# ifusb_l.net
KiCad netlist of a schematic drawn in EAGLE
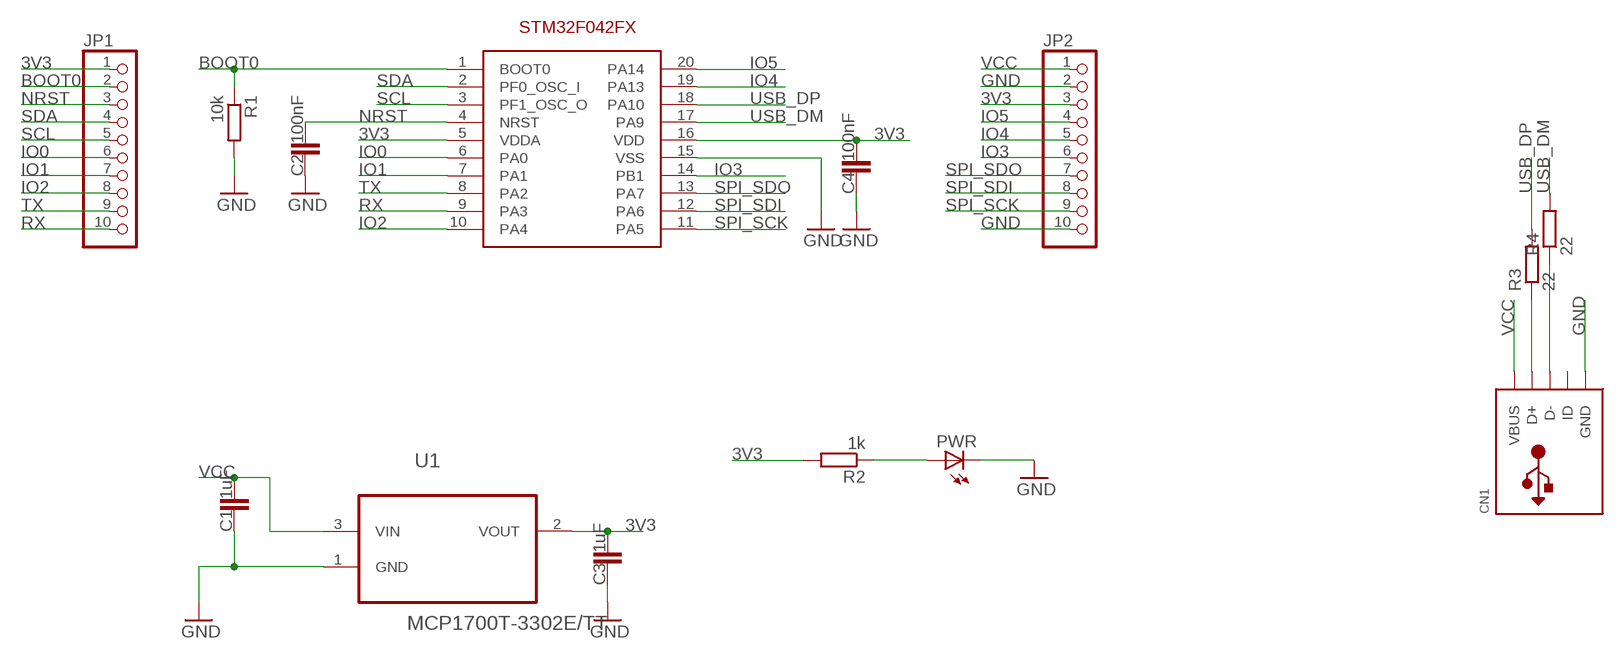
[diagram p0: schematic, sheet 1]

(export (version "E")
  (design (tool "Eeschema 10.0.6"))
  (components
    (comp (ref "C1")
      (value "1uF")
      (footprint "eagle-import:C0603K")
      (libsource (lib "eagle-import") (part "C-EUC0603K"))
    )
    (comp (ref "C2")
      (value "100nF")
      (footprint "eagle-import:C0603K")
      (libsource (lib "eagle-import") (part "C-EUC0603K"))
    )
    (comp (ref "C3")
      (value "1uF")
      (footprint "eagle-import:C0603K")
      (libsource (lib "eagle-import") (part "C-EUC0603K"))
    )
    (comp (ref "C4")
      (value "100nF")
      (footprint "eagle-import:C0603K")
      (libsource (lib "eagle-import") (part "C-EUC0603K"))
    )
    (comp (ref "CN1")
      (value "USBMOLEX")
      (footprint "eagle-import:USB-MINIB-THM-MOLEX")
      (libsource (lib "eagle-import") (part "USBMOLEX"))
    )
    (comp (ref "JP1")
      (value "HEADER-1X10ROUND")
      (footprint "eagle-import:1X10_ROUND")
      (libsource (lib "eagle-import") (part "HEADER-1X10ROUND"))
    )
    (comp (ref "JP2")
      (value "HEADER-1X10ROUND")
      (footprint "eagle-import:1X10_ROUND")
      (libsource (lib "eagle-import") (part "HEADER-1X10ROUND"))
    )
    (comp (ref "PWR")
      (value "LEDCHIP-LED0603")
      (footprint "eagle-import:CHIP-LED0603")
      (libsource (lib "eagle-import") (part "LEDCHIP-LED0603"))
    )
    (comp (ref "R1")
      (value "10k")
      (footprint "eagle-import:R0603")
      (libsource (lib "eagle-import") (part "R-EU_R0603"))
    )
    (comp (ref "R2")
      (value "1k")
      (footprint "eagle-import:R0603")
      (libsource (lib "eagle-import") (part "R-EU_R0603"))
    )
    (comp (ref "R3")
      (value "22")
      (footprint "eagle-import:R0603")
      (libsource (lib "eagle-import") (part "R-EU_R0603"))
    )
    (comp (ref "R4")
      (value "22")
      (footprint "eagle-import:R0603")
      (libsource (lib "eagle-import") (part "R-EU_R0603"))
    )
    (comp (ref "U1")
      (value "MCP1700T-3302E/TT")
      (footprint "eagle-import:SOT95P237X112-3N")
      (libsource (lib "eagle-import") (part "MCP1700T-3302E/TT"))
    )
    (comp (ref "U2")
      (value "STM32F042FX")
      (footprint "eagle-import:TSSOP20")
      (libsource (lib "eagle-import") (part "STM32F042FX"))
    )
  )
  (nets
    (net (code "1") (name "/3V3") (class "Default")
      (node (ref "C3") (pin "2") (pinfunction "2_2") (pintype "passive"))
      (node (ref "C4") (pin "2") (pinfunction "2_2") (pintype "passive"))
      (node (ref "JP1") (pin "1") (pinfunction "1_1") (pintype "passive"))
      (node (ref "JP2") (pin "3") (pinfunction "3_3") (pintype "passive"))
      (node (ref "R2") (pin "2") (pinfunction "2_2") (pintype "passive"))
      (node (ref "U1") (pin "2") (pinfunction "VOUT_2") (pintype "output"))
      (node (ref "U2") (pin "16") (pinfunction "VDD_16") (pintype "power_in"))
      (node (ref "U2") (pin "5") (pinfunction "VDDA_5") (pintype "power_in"))
    )
    (net (code "2") (name "/BOOT0") (class "Default")
      (node (ref "JP1") (pin "2") (pinfunction "2_2") (pintype "passive"))
      (node (ref "R1") (pin "1") (pinfunction "1_1") (pintype "passive"))
      (node (ref "U2") (pin "1") (pinfunction "BOOT0_1") (pintype "bidirectional"))
    )
    (net (code "3") (name "/IO0") (class "Default")
      (node (ref "JP1") (pin "6") (pinfunction "6_6") (pintype "passive"))
      (node (ref "U2") (pin "6") (pinfunction "PA0_6") (pintype "bidirectional"))
    )
    (net (code "4") (name "/IO1") (class "Default")
      (node (ref "JP1") (pin "7") (pinfunction "7_7") (pintype "passive"))
      (node (ref "U2") (pin "7") (pinfunction "PA1_7") (pintype "bidirectional"))
    )
    (net (code "5") (name "/IO2") (class "Default")
      (node (ref "JP1") (pin "8") (pinfunction "8_8") (pintype "passive"))
      (node (ref "U2") (pin "10") (pinfunction "PA4_10") (pintype "bidirectional"))
    )
    (net (code "6") (name "/IO3") (class "Default")
      (node (ref "JP2") (pin "6") (pinfunction "6_6") (pintype "passive"))
      (node (ref "U2") (pin "14") (pinfunction "PB1_14") (pintype "bidirectional"))
    )
    (net (code "7") (name "/IO4") (class "Default")
      (node (ref "JP2") (pin "5") (pinfunction "5_5") (pintype "passive"))
      (node (ref "U2") (pin "19") (pinfunction "PA13_19") (pintype "bidirectional"))
    )
    (net (code "8") (name "/IO5") (class "Default")
      (node (ref "JP2") (pin "4") (pinfunction "4_4") (pintype "passive"))
      (node (ref "U2") (pin "20") (pinfunction "PA14_20") (pintype "bidirectional"))
    )
    (net (code "9") (name "/NRST") (class "Default")
      (node (ref "C2") (pin "2") (pinfunction "2_2") (pintype "passive"))
      (node (ref "JP1") (pin "3") (pinfunction "3_3") (pintype "passive"))
      (node (ref "U2") (pin "4") (pinfunction "NRST_4") (pintype "input"))
    )
    (net (code "10") (name "/RX") (class "Default")
      (node (ref "JP1") (pin "10") (pinfunction "10_10") (pintype "passive"))
      (node (ref "U2") (pin "9") (pinfunction "PA3_9") (pintype "bidirectional"))
    )
    (net (code "11") (name "/SCL") (class "Default")
      (node (ref "JP1") (pin "5") (pinfunction "5_5") (pintype "passive"))
      (node (ref "U2") (pin "3") (pinfunction "PF1_OSC_O_3") (pintype "bidirectional"))
    )
    (net (code "12") (name "/SDA") (class "Default")
      (node (ref "JP1") (pin "4") (pinfunction "4_4") (pintype "passive"))
      (node (ref "U2") (pin "2") (pinfunction "PF0_OSC_I_2") (pintype "bidirectional"))
    )
    (net (code "13") (name "/SPI_SCK") (class "Default")
      (node (ref "JP2") (pin "9") (pinfunction "9_9") (pintype "passive"))
      (node (ref "U2") (pin "11") (pinfunction "PA5_11") (pintype "bidirectional"))
    )
    (net (code "14") (name "/SPI_SDI") (class "Default")
      (node (ref "JP2") (pin "8") (pinfunction "8_8") (pintype "passive"))
      (node (ref "U2") (pin "12") (pinfunction "PA6_12") (pintype "bidirectional"))
    )
    (net (code "15") (name "/SPI_SDO") (class "Default")
      (node (ref "JP2") (pin "7") (pinfunction "7_7") (pintype "passive"))
      (node (ref "U2") (pin "13") (pinfunction "PA7_13") (pintype "bidirectional"))
    )
    (net (code "16") (name "/TX") (class "Default")
      (node (ref "JP1") (pin "9") (pinfunction "9_9") (pintype "passive"))
      (node (ref "U2") (pin "8") (pinfunction "PA2_8") (pintype "bidirectional"))
    )
    (net (code "17") (name "/USB_DM") (class "Default")
      (node (ref "R4") (pin "2") (pinfunction "2_2") (pintype "passive"))
      (node (ref "U2") (pin "17") (pinfunction "PA9_17") (pintype "bidirectional"))
    )
    (net (code "18") (name "/USB_DP") (class "Default")
      (node (ref "R3") (pin "2") (pinfunction "2_2") (pintype "passive"))
      (node (ref "U2") (pin "18") (pinfunction "PA10_18") (pintype "bidirectional"))
    )
    (net (code "19") (name "/VCC") (class "Default")
      (node (ref "C1") (pin "2") (pinfunction "2_2") (pintype "passive"))
      (node (ref "CN1") (pin "VBUS") (pinfunction "VBUS_VBUS") (pintype "power_in"))
      (node (ref "JP2") (pin "1") (pinfunction "1_1") (pintype "passive"))
      (node (ref "U1") (pin "3") (pinfunction "VIN_3") (pintype "input"))
    )
    (net (code "20") (name "GND") (class "Default")
      (node (ref "C1") (pin "1") (pinfunction "1_1") (pintype "passive"))
      (node (ref "C2") (pin "1") (pinfunction "1_1") (pintype "passive"))
      (node (ref "C3") (pin "1") (pinfunction "1_1") (pintype "passive"))
      (node (ref "C4") (pin "1") (pinfunction "1_1") (pintype "passive"))
      (node (ref "CN1") (pin "GND") (pinfunction "GND_GND") (pintype "power_in"))
      (node (ref "JP2") (pin "10") (pinfunction "10_10") (pintype "passive"))
      (node (ref "JP2") (pin "2") (pinfunction "2_2") (pintype "passive"))
      (node (ref "PWR") (pin "C") (pinfunction "C_C") (pintype "passive"))
      (node (ref "R1") (pin "2") (pinfunction "2_2") (pintype "passive"))
      (node (ref "U1") (pin "1") (pinfunction "GND_1") (pintype "passive"))
      (node (ref "U2") (pin "15") (pinfunction "VSS_15") (pintype "power_in"))
    )
    (net (code "21") (name "Net-(CN1-PadD+)") (class "Default")
      (node (ref "CN1") (pin "D+") (pinfunction "D+_D+") (pintype "bidirectional"))
      (node (ref "R3") (pin "1") (pinfunction "1_1") (pintype "passive"))
    )
    (net (code "22") (name "Net-(CN1-PadD-)") (class "Default")
      (node (ref "CN1") (pin "D-") (pinfunction "D-_D-") (pintype "bidirectional"))
      (node (ref "R4") (pin "1") (pinfunction "1_1") (pintype "passive"))
    )
    (net (code "23") (name "Net-(PWR-PadA)") (class "Default")
      (node (ref "PWR") (pin "A") (pinfunction "A_A") (pintype "passive"))
      (node (ref "R2") (pin "1") (pinfunction "1_1") (pintype "passive"))
    )
    (net (code "24") (name "unconnected-(CN1-PadID)") (class "Default")
      (node (ref "CN1") (pin "ID") (pinfunction "ID_ID") (pintype "bidirectional"))
    )
  )
)
